# STRAIGT_SENSOR_NOMUX_16.net
KiCad netlist of a schematic drawn in EAGLE
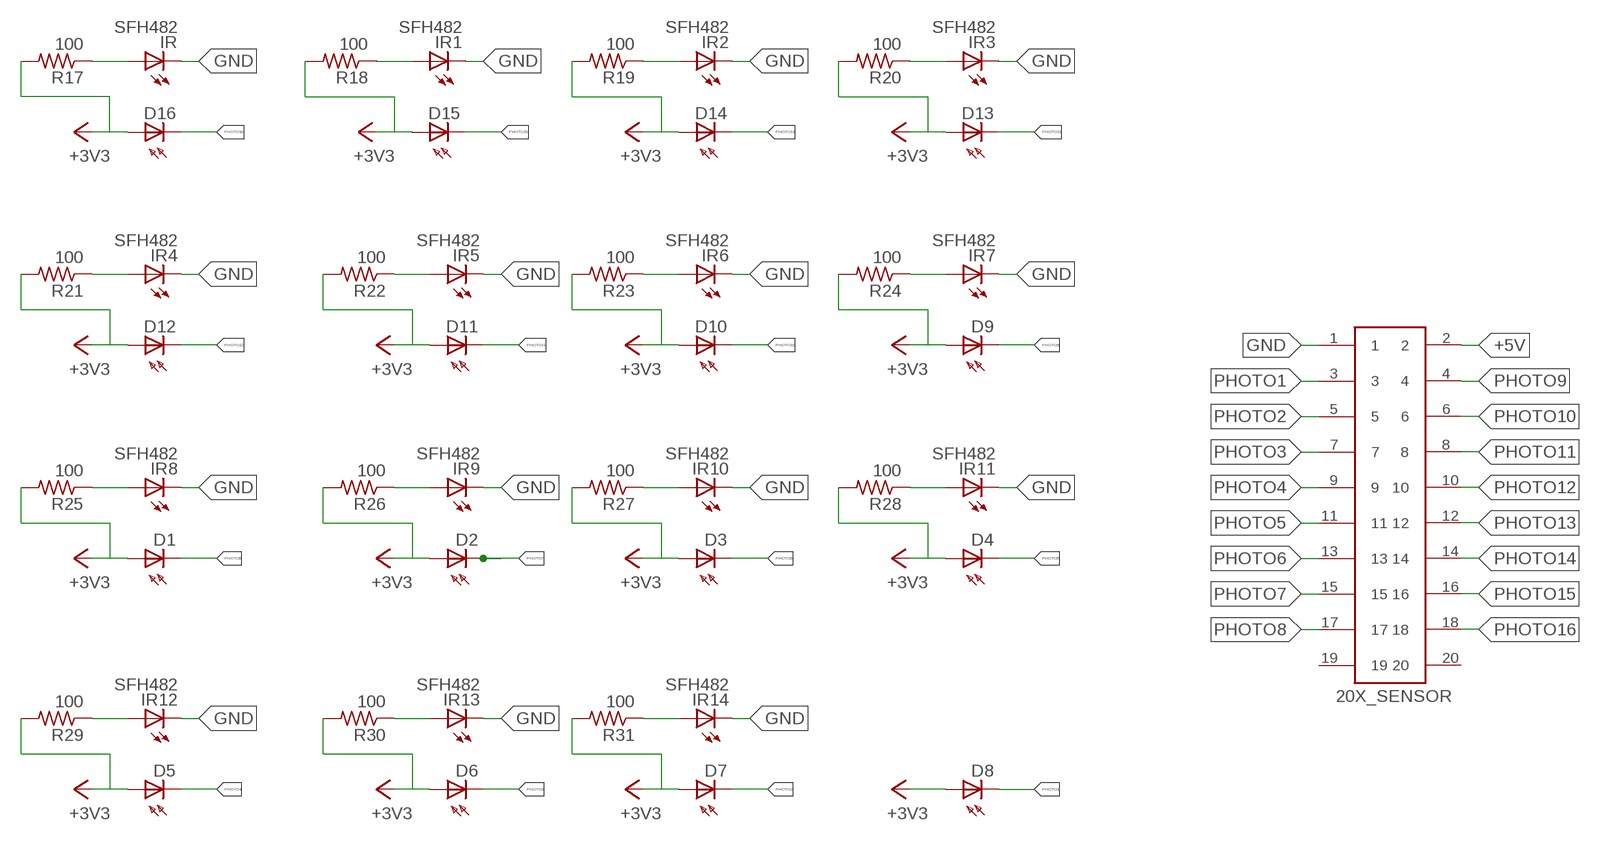
[diagram p0: schematic, sheet 1]

(export (version "E")
  (design (tool "Eeschema 10.0.6"))
  (components
    (comp (ref "20X_SENSOR")
      (value "61202022021")
      (footprint "eagle-import:61202022021")
      (libsource (lib "eagle-import") (part "61202022021"))
    )
    (comp (ref "D1")
      (value "Photo0")
      (footprint "eagle-import:BPX65")
      (fields (field (name "MPN") "BPX65."))
      (libsource (lib "eagle-import") (part "BPX65"))
    )
    (comp (ref "D2")
      (value "Photo1")
      (footprint "eagle-import:BPX65")
      (fields (field (name "MPN") "BPX65."))
      (libsource (lib "eagle-import") (part "BPX65"))
    )
    (comp (ref "D3")
      (value "Photo2")
      (footprint "eagle-import:BPX65")
      (fields (field (name "MPN") "BPX65."))
      (libsource (lib "eagle-import") (part "BPX65"))
    )
    (comp (ref "D4")
      (value "Photo3")
      (footprint "eagle-import:BPX65")
      (fields (field (name "MPN") "BPX65."))
      (libsource (lib "eagle-import") (part "BPX65"))
    )
    (comp (ref "D5")
      (value "Photo4")
      (footprint "eagle-import:BPX65")
      (fields (field (name "MPN") "BPX65."))
      (libsource (lib "eagle-import") (part "BPX65"))
    )
    (comp (ref "D6")
      (value "Photo5")
      (footprint "eagle-import:BPX65")
      (fields (field (name "MPN") "BPX65."))
      (libsource (lib "eagle-import") (part "BPX65"))
    )
    (comp (ref "D7")
      (value "Photo6")
      (footprint "eagle-import:BPX65")
      (fields (field (name "MPN") "BPX65."))
      (libsource (lib "eagle-import") (part "BPX65"))
    )
    (comp (ref "D8")
      (value "Photo7")
      (footprint "eagle-import:BPX65")
      (fields (field (name "MPN") "BPX65."))
      (libsource (lib "eagle-import") (part "BPX65"))
    )
    (comp (ref "D9")
      (value "Photo0")
      (footprint "eagle-import:BPX65")
      (fields (field (name "MPN") "BPX65."))
      (libsource (lib "eagle-import") (part "BPX65"))
    )
    (comp (ref "D10")
      (value "Photo0")
      (footprint "eagle-import:BPX65")
      (fields (field (name "MPN") "BPX65."))
      (libsource (lib "eagle-import") (part "BPX65"))
    )
    (comp (ref "D11")
      (value "Photo0")
      (footprint "eagle-import:BPX65")
      (fields (field (name "MPN") "BPX65."))
      (libsource (lib "eagle-import") (part "BPX65"))
    )
    (comp (ref "D12")
      (value "Photo0")
      (footprint "eagle-import:BPX65")
      (fields (field (name "MPN") "BPX65."))
      (libsource (lib "eagle-import") (part "BPX65"))
    )
    (comp (ref "D13")
      (value "Photo0")
      (footprint "eagle-import:BPX65")
      (fields (field (name "MPN") "BPX65."))
      (libsource (lib "eagle-import") (part "BPX65"))
    )
    (comp (ref "D14")
      (value "Photo0")
      (footprint "eagle-import:BPX65")
      (fields (field (name "MPN") "BPX65."))
      (libsource (lib "eagle-import") (part "BPX65"))
    )
    (comp (ref "D15")
      (value "Photo0")
      (footprint "eagle-import:BPX65")
      (fields (field (name "MPN") "BPX65."))
      (libsource (lib "eagle-import") (part "BPX65"))
    )
    (comp (ref "D16")
      (value "Photo0")
      (footprint "eagle-import:BPX65")
      (fields (field (name "MPN") "BPX65."))
      (libsource (lib "eagle-import") (part "BPX65"))
    )
    (comp (ref "IR")
      (value "SFH482")
      (footprint "eagle-import:SFH482")
      (libsource (lib "eagle-import") (part "SFH482"))
    )
    (comp (ref "IR1")
      (value "SFH482")
      (footprint "eagle-import:SFH482")
      (libsource (lib "eagle-import") (part "SFH482"))
    )
    (comp (ref "IR2")
      (value "SFH482")
      (footprint "eagle-import:SFH482")
      (libsource (lib "eagle-import") (part "SFH482"))
    )
    (comp (ref "IR3")
      (value "SFH482")
      (footprint "eagle-import:SFH482")
      (libsource (lib "eagle-import") (part "SFH482"))
    )
    (comp (ref "IR4")
      (value "SFH482")
      (footprint "eagle-import:SFH482")
      (libsource (lib "eagle-import") (part "SFH482"))
    )
    (comp (ref "IR5")
      (value "SFH482")
      (footprint "eagle-import:SFH482")
      (libsource (lib "eagle-import") (part "SFH482"))
    )
    (comp (ref "IR6")
      (value "SFH482")
      (footprint "eagle-import:SFH482")
      (libsource (lib "eagle-import") (part "SFH482"))
    )
    (comp (ref "IR7")
      (value "SFH482")
      (footprint "eagle-import:SFH482")
      (libsource (lib "eagle-import") (part "SFH482"))
    )
    (comp (ref "IR8")
      (value "SFH482")
      (footprint "eagle-import:SFH482")
      (libsource (lib "eagle-import") (part "SFH482"))
    )
    (comp (ref "IR9")
      (value "SFH482")
      (footprint "eagle-import:SFH482")
      (libsource (lib "eagle-import") (part "SFH482"))
    )
    (comp (ref "IR10")
      (value "SFH482")
      (footprint "eagle-import:SFH482")
      (libsource (lib "eagle-import") (part "SFH482"))
    )
    (comp (ref "IR11")
      (value "SFH482")
      (footprint "eagle-import:SFH482")
      (libsource (lib "eagle-import") (part "SFH482"))
    )
    (comp (ref "IR12")
      (value "SFH482")
      (footprint "eagle-import:SFH482")
      (libsource (lib "eagle-import") (part "SFH482"))
    )
    (comp (ref "IR13")
      (value "SFH482")
      (footprint "eagle-import:SFH482")
      (libsource (lib "eagle-import") (part "SFH482"))
    )
    (comp (ref "IR14")
      (value "SFH482")
      (footprint "eagle-import:SFH482")
      (libsource (lib "eagle-import") (part "SFH482"))
    )
    (comp (ref "R17")
      (value "100")
      (footprint "eagle-import:0207_10")
      (libsource (lib "eagle-import") (part "R-US_0207/10"))
    )
    (comp (ref "R18")
      (value "100")
      (footprint "eagle-import:0207_10")
      (libsource (lib "eagle-import") (part "R-US_0207/10"))
    )
    (comp (ref "R19")
      (value "100")
      (footprint "eagle-import:0207_10")
      (libsource (lib "eagle-import") (part "R-US_0207/10"))
    )
    (comp (ref "R20")
      (value "100")
      (footprint "eagle-import:0207_10")
      (libsource (lib "eagle-import") (part "R-US_0207/10"))
    )
    (comp (ref "R21")
      (value "100")
      (footprint "eagle-import:0207_10")
      (libsource (lib "eagle-import") (part "R-US_0207/10"))
    )
    (comp (ref "R22")
      (value "100")
      (footprint "eagle-import:0207_10")
      (libsource (lib "eagle-import") (part "R-US_0207/10"))
    )
    (comp (ref "R23")
      (value "100")
      (footprint "eagle-import:0207_10")
      (libsource (lib "eagle-import") (part "R-US_0207/10"))
    )
    (comp (ref "R24")
      (value "100")
      (footprint "eagle-import:0207_10")
      (libsource (lib "eagle-import") (part "R-US_0207/10"))
    )
    (comp (ref "R25")
      (value "100")
      (footprint "eagle-import:0207_10")
      (libsource (lib "eagle-import") (part "R-US_0207/10"))
    )
    (comp (ref "R26")
      (value "100")
      (footprint "eagle-import:0207_10")
      (libsource (lib "eagle-import") (part "R-US_0207/10"))
    )
    (comp (ref "R27")
      (value "100")
      (footprint "eagle-import:0207_10")
      (libsource (lib "eagle-import") (part "R-US_0207/10"))
    )
    (comp (ref "R28")
      (value "100")
      (footprint "eagle-import:0207_10")
      (libsource (lib "eagle-import") (part "R-US_0207/10"))
    )
    (comp (ref "R29")
      (value "100")
      (footprint "eagle-import:0207_10")
      (libsource (lib "eagle-import") (part "R-US_0207/10"))
    )
    (comp (ref "R30")
      (value "100")
      (footprint "eagle-import:0207_10")
      (libsource (lib "eagle-import") (part "R-US_0207/10"))
    )
    (comp (ref "R31")
      (value "100")
      (footprint "eagle-import:0207_10")
      (libsource (lib "eagle-import") (part "R-US_0207/10"))
    )
  )
  (nets
    (net (code "1") (name "+3V3") (class "Default")
      (node (ref "D1") (pin "A") (pinfunction "A_A") (pintype "passive"))
      (node (ref "D10") (pin "A") (pinfunction "A_A") (pintype "passive"))
      (node (ref "D11") (pin "A") (pinfunction "A_A") (pintype "passive"))
      (node (ref "D12") (pin "A") (pinfunction "A_A") (pintype "passive"))
      (node (ref "D13") (pin "A") (pinfunction "A_A") (pintype "passive"))
      (node (ref "D14") (pin "A") (pinfunction "A_A") (pintype "passive"))
      (node (ref "D15") (pin "A") (pinfunction "A_A") (pintype "passive"))
      (node (ref "D16") (pin "A") (pinfunction "A_A") (pintype "passive"))
      (node (ref "D2") (pin "A") (pinfunction "A_A") (pintype "passive"))
      (node (ref "D3") (pin "A") (pinfunction "A_A") (pintype "passive"))
      (node (ref "D4") (pin "A") (pinfunction "A_A") (pintype "passive"))
      (node (ref "D5") (pin "A") (pinfunction "A_A") (pintype "passive"))
      (node (ref "D6") (pin "A") (pinfunction "A_A") (pintype "passive"))
      (node (ref "D7") (pin "A") (pinfunction "A_A") (pintype "passive"))
      (node (ref "D8") (pin "A") (pinfunction "A_A") (pintype "passive"))
      (node (ref "D9") (pin "A") (pinfunction "A_A") (pintype "passive"))
      (node (ref "R17") (pin "2") (pinfunction "2_2") (pintype "passive"))
      (node (ref "R18") (pin "2") (pinfunction "2_2") (pintype "passive"))
      (node (ref "R19") (pin "2") (pinfunction "2_2") (pintype "passive"))
      (node (ref "R20") (pin "2") (pinfunction "2_2") (pintype "passive"))
      (node (ref "R21") (pin "2") (pinfunction "2_2") (pintype "passive"))
      (node (ref "R22") (pin "2") (pinfunction "2_2") (pintype "passive"))
      (node (ref "R23") (pin "2") (pinfunction "2_2") (pintype "passive"))
      (node (ref "R24") (pin "2") (pinfunction "2_2") (pintype "passive"))
      (node (ref "R25") (pin "2") (pinfunction "2_2") (pintype "passive"))
      (node (ref "R26") (pin "2") (pinfunction "2_2") (pintype "passive"))
      (node (ref "R27") (pin "2") (pinfunction "2_2") (pintype "passive"))
      (node (ref "R28") (pin "2") (pinfunction "2_2") (pintype "passive"))
      (node (ref "R29") (pin "2") (pinfunction "2_2") (pintype "passive"))
      (node (ref "R30") (pin "2") (pinfunction "2_2") (pintype "passive"))
      (node (ref "R31") (pin "2") (pinfunction "2_2") (pintype "passive"))
    )
    (net (code "2") (name "+5V") (class "Default")
      (node (ref "20X_SENSOR") (pin "2") (pinfunction "2_2") (pintype "passive"))
    )
    (net (code "3") (name "GND") (class "Default")
      (node (ref "20X_SENSOR") (pin "1") (pinfunction "1_1") (pintype "passive"))
      (node (ref "IR") (pin "K") (pinfunction "C_K") (pintype "passive"))
      (node (ref "IR1") (pin "K") (pinfunction "C_K") (pintype "passive"))
      (node (ref "IR10") (pin "K") (pinfunction "C_K") (pintype "passive"))
      (node (ref "IR11") (pin "K") (pinfunction "C_K") (pintype "passive"))
      (node (ref "IR12") (pin "K") (pinfunction "C_K") (pintype "passive"))
      (node (ref "IR13") (pin "K") (pinfunction "C_K") (pintype "passive"))
      (node (ref "IR14") (pin "K") (pinfunction "C_K") (pintype "passive"))
      (node (ref "IR2") (pin "K") (pinfunction "C_K") (pintype "passive"))
      (node (ref "IR3") (pin "K") (pinfunction "C_K") (pintype "passive"))
      (node (ref "IR4") (pin "K") (pinfunction "C_K") (pintype "passive"))
      (node (ref "IR5") (pin "K") (pinfunction "C_K") (pintype "passive"))
      (node (ref "IR6") (pin "K") (pinfunction "C_K") (pintype "passive"))
      (node (ref "IR7") (pin "K") (pinfunction "C_K") (pintype "passive"))
      (node (ref "IR8") (pin "K") (pinfunction "C_K") (pintype "passive"))
      (node (ref "IR9") (pin "K") (pinfunction "C_K") (pintype "passive"))
    )
    (net (code "4") (name "Net-(IR-PadA)") (class "Default")
      (node (ref "IR") (pin "A") (pinfunction "A_A") (pintype "passive"))
      (node (ref "R17") (pin "1") (pinfunction "1_1") (pintype "passive"))
    )
    (net (code "5") (name "Net-(IR1-PadA)") (class "Default")
      (node (ref "IR1") (pin "A") (pinfunction "A_A") (pintype "passive"))
      (node (ref "R18") (pin "1") (pinfunction "1_1") (pintype "passive"))
    )
    (net (code "6") (name "Net-(IR2-PadA)") (class "Default")
      (node (ref "IR2") (pin "A") (pinfunction "A_A") (pintype "passive"))
      (node (ref "R19") (pin "1") (pinfunction "1_1") (pintype "passive"))
    )
    (net (code "7") (name "Net-(IR3-PadA)") (class "Default")
      (node (ref "IR3") (pin "A") (pinfunction "A_A") (pintype "passive"))
      (node (ref "R20") (pin "1") (pinfunction "1_1") (pintype "passive"))
    )
    (net (code "8") (name "Net-(IR4-PadA)") (class "Default")
      (node (ref "IR4") (pin "A") (pinfunction "A_A") (pintype "passive"))
      (node (ref "R21") (pin "1") (pinfunction "1_1") (pintype "passive"))
    )
    (net (code "9") (name "Net-(IR5-PadA)") (class "Default")
      (node (ref "IR5") (pin "A") (pinfunction "A_A") (pintype "passive"))
      (node (ref "R22") (pin "1") (pinfunction "1_1") (pintype "passive"))
    )
    (net (code "10") (name "Net-(IR6-PadA)") (class "Default")
      (node (ref "IR6") (pin "A") (pinfunction "A_A") (pintype "passive"))
      (node (ref "R23") (pin "1") (pinfunction "1_1") (pintype "passive"))
    )
    (net (code "11") (name "Net-(IR7-PadA)") (class "Default")
      (node (ref "IR7") (pin "A") (pinfunction "A_A") (pintype "passive"))
      (node (ref "R24") (pin "1") (pinfunction "1_1") (pintype "passive"))
    )
    (net (code "12") (name "Net-(IR8-PadA)") (class "Default")
      (node (ref "IR8") (pin "A") (pinfunction "A_A") (pintype "passive"))
      (node (ref "R25") (pin "1") (pinfunction "1_1") (pintype "passive"))
    )
    (net (code "13") (name "Net-(IR9-PadA)") (class "Default")
      (node (ref "IR9") (pin "A") (pinfunction "A_A") (pintype "passive"))
      (node (ref "R26") (pin "1") (pinfunction "1_1") (pintype "passive"))
    )
    (net (code "14") (name "Net-(IR10-PadA)") (class "Default")
      (node (ref "IR10") (pin "A") (pinfunction "A_A") (pintype "passive"))
      (node (ref "R27") (pin "1") (pinfunction "1_1") (pintype "passive"))
    )
    (net (code "15") (name "Net-(IR11-PadA)") (class "Default")
      (node (ref "IR11") (pin "A") (pinfunction "A_A") (pintype "passive"))
      (node (ref "R28") (pin "1") (pinfunction "1_1") (pintype "passive"))
    )
    (net (code "16") (name "Net-(IR12-PadA)") (class "Default")
      (node (ref "IR12") (pin "A") (pinfunction "A_A") (pintype "passive"))
      (node (ref "R29") (pin "1") (pinfunction "1_1") (pintype "passive"))
    )
    (net (code "17") (name "Net-(IR13-PadA)") (class "Default")
      (node (ref "IR13") (pin "A") (pinfunction "A_A") (pintype "passive"))
      (node (ref "R30") (pin "1") (pinfunction "1_1") (pintype "passive"))
    )
    (net (code "18") (name "Net-(IR14-PadA)") (class "Default")
      (node (ref "IR14") (pin "A") (pinfunction "A_A") (pintype "passive"))
      (node (ref "R31") (pin "1") (pinfunction "1_1") (pintype "passive"))
    )
    (net (code "19") (name "PHOTO1") (class "Default")
      (node (ref "20X_SENSOR") (pin "3") (pinfunction "3_3") (pintype "passive"))
      (node (ref "D8") (pin "K") (pinfunction "C_K") (pintype "passive"))
    )
    (net (code "20") (name "PHOTO2") (class "Default")
      (node (ref "20X_SENSOR") (pin "5") (pinfunction "5_5") (pintype "passive"))
      (node (ref "D7") (pin "K") (pinfunction "C_K") (pintype "passive"))
    )
    (net (code "21") (name "PHOTO3") (class "Default")
      (node (ref "20X_SENSOR") (pin "7") (pinfunction "7_7") (pintype "passive"))
      (node (ref "D6") (pin "K") (pinfunction "C_K") (pintype "passive"))
    )
    (net (code "22") (name "PHOTO4") (class "Default")
      (node (ref "20X_SENSOR") (pin "9") (pinfunction "9_9") (pintype "passive"))
      (node (ref "D5") (pin "K") (pinfunction "C_K") (pintype "passive"))
    )
    (net (code "23") (name "PHOTO5") (class "Default")
      (node (ref "20X_SENSOR") (pin "11") (pinfunction "11_11") (pintype "passive"))
      (node (ref "D4") (pin "K") (pinfunction "C_K") (pintype "passive"))
    )
    (net (code "24") (name "PHOTO6") (class "Default")
      (node (ref "20X_SENSOR") (pin "13") (pinfunction "13_13") (pintype "passive"))
      (node (ref "D3") (pin "K") (pinfunction "C_K") (pintype "passive"))
    )
    (net (code "25") (name "PHOTO7") (class "Default")
      (node (ref "20X_SENSOR") (pin "15") (pinfunction "15_15") (pintype "passive"))
      (node (ref "D2") (pin "K") (pinfunction "C_K") (pintype "passive"))
    )
    (net (code "26") (name "PHOTO8") (class "Default")
      (node (ref "20X_SENSOR") (pin "17") (pinfunction "17_17") (pintype "passive"))
      (node (ref "D1") (pin "K") (pinfunction "C_K") (pintype "passive"))
    )
    (net (code "27") (name "PHOTO9") (class "Default")
      (node (ref "20X_SENSOR") (pin "4") (pinfunction "4_4") (pintype "passive"))
      (node (ref "D9") (pin "K") (pinfunction "C_K") (pintype "passive"))
    )
    (net (code "28") (name "PHOTO10") (class "Default")
      (node (ref "20X_SENSOR") (pin "6") (pinfunction "6_6") (pintype "passive"))
      (node (ref "D10") (pin "K") (pinfunction "C_K") (pintype "passive"))
    )
    (net (code "29") (name "PHOTO11") (class "Default")
      (node (ref "20X_SENSOR") (pin "8") (pinfunction "8_8") (pintype "passive"))
      (node (ref "D11") (pin "K") (pinfunction "C_K") (pintype "passive"))
    )
    (net (code "30") (name "PHOTO12") (class "Default")
      (node (ref "20X_SENSOR") (pin "10") (pinfunction "10_10") (pintype "passive"))
      (node (ref "D12") (pin "K") (pinfunction "C_K") (pintype "passive"))
    )
    (net (code "31") (name "PHOTO13") (class "Default")
      (node (ref "20X_SENSOR") (pin "12") (pinfunction "12_12") (pintype "passive"))
      (node (ref "D13") (pin "K") (pinfunction "C_K") (pintype "passive"))
    )
    (net (code "32") (name "PHOTO14") (class "Default")
      (node (ref "20X_SENSOR") (pin "14") (pinfunction "14_14") (pintype "passive"))
      (node (ref "D14") (pin "K") (pinfunction "C_K") (pintype "passive"))
    )
    (net (code "33") (name "PHOTO15") (class "Default")
      (node (ref "20X_SENSOR") (pin "16") (pinfunction "16_16") (pintype "passive"))
      (node (ref "D15") (pin "K") (pinfunction "C_K") (pintype "passive"))
    )
    (net (code "34") (name "PHOTO16") (class "Default")
      (node (ref "20X_SENSOR") (pin "18") (pinfunction "18_18") (pintype "passive"))
      (node (ref "D16") (pin "K") (pinfunction "C_K") (pintype "passive"))
    )
    (net (code "35") (name "unconnected-(20X_SENSOR-Pad19)") (class "Default")
      (node (ref "20X_SENSOR") (pin "19") (pinfunction "19_19") (pintype "passive"))
    )
    (net (code "36") (name "unconnected-(20X_SENSOR-Pad20)") (class "Default")
      (node (ref "20X_SENSOR") (pin "20") (pinfunction "20_20") (pintype "passive"))
    )
  )
)
